# reduktor_ultra_light.net
KiCad netlist of a schematic drawn in EAGLE
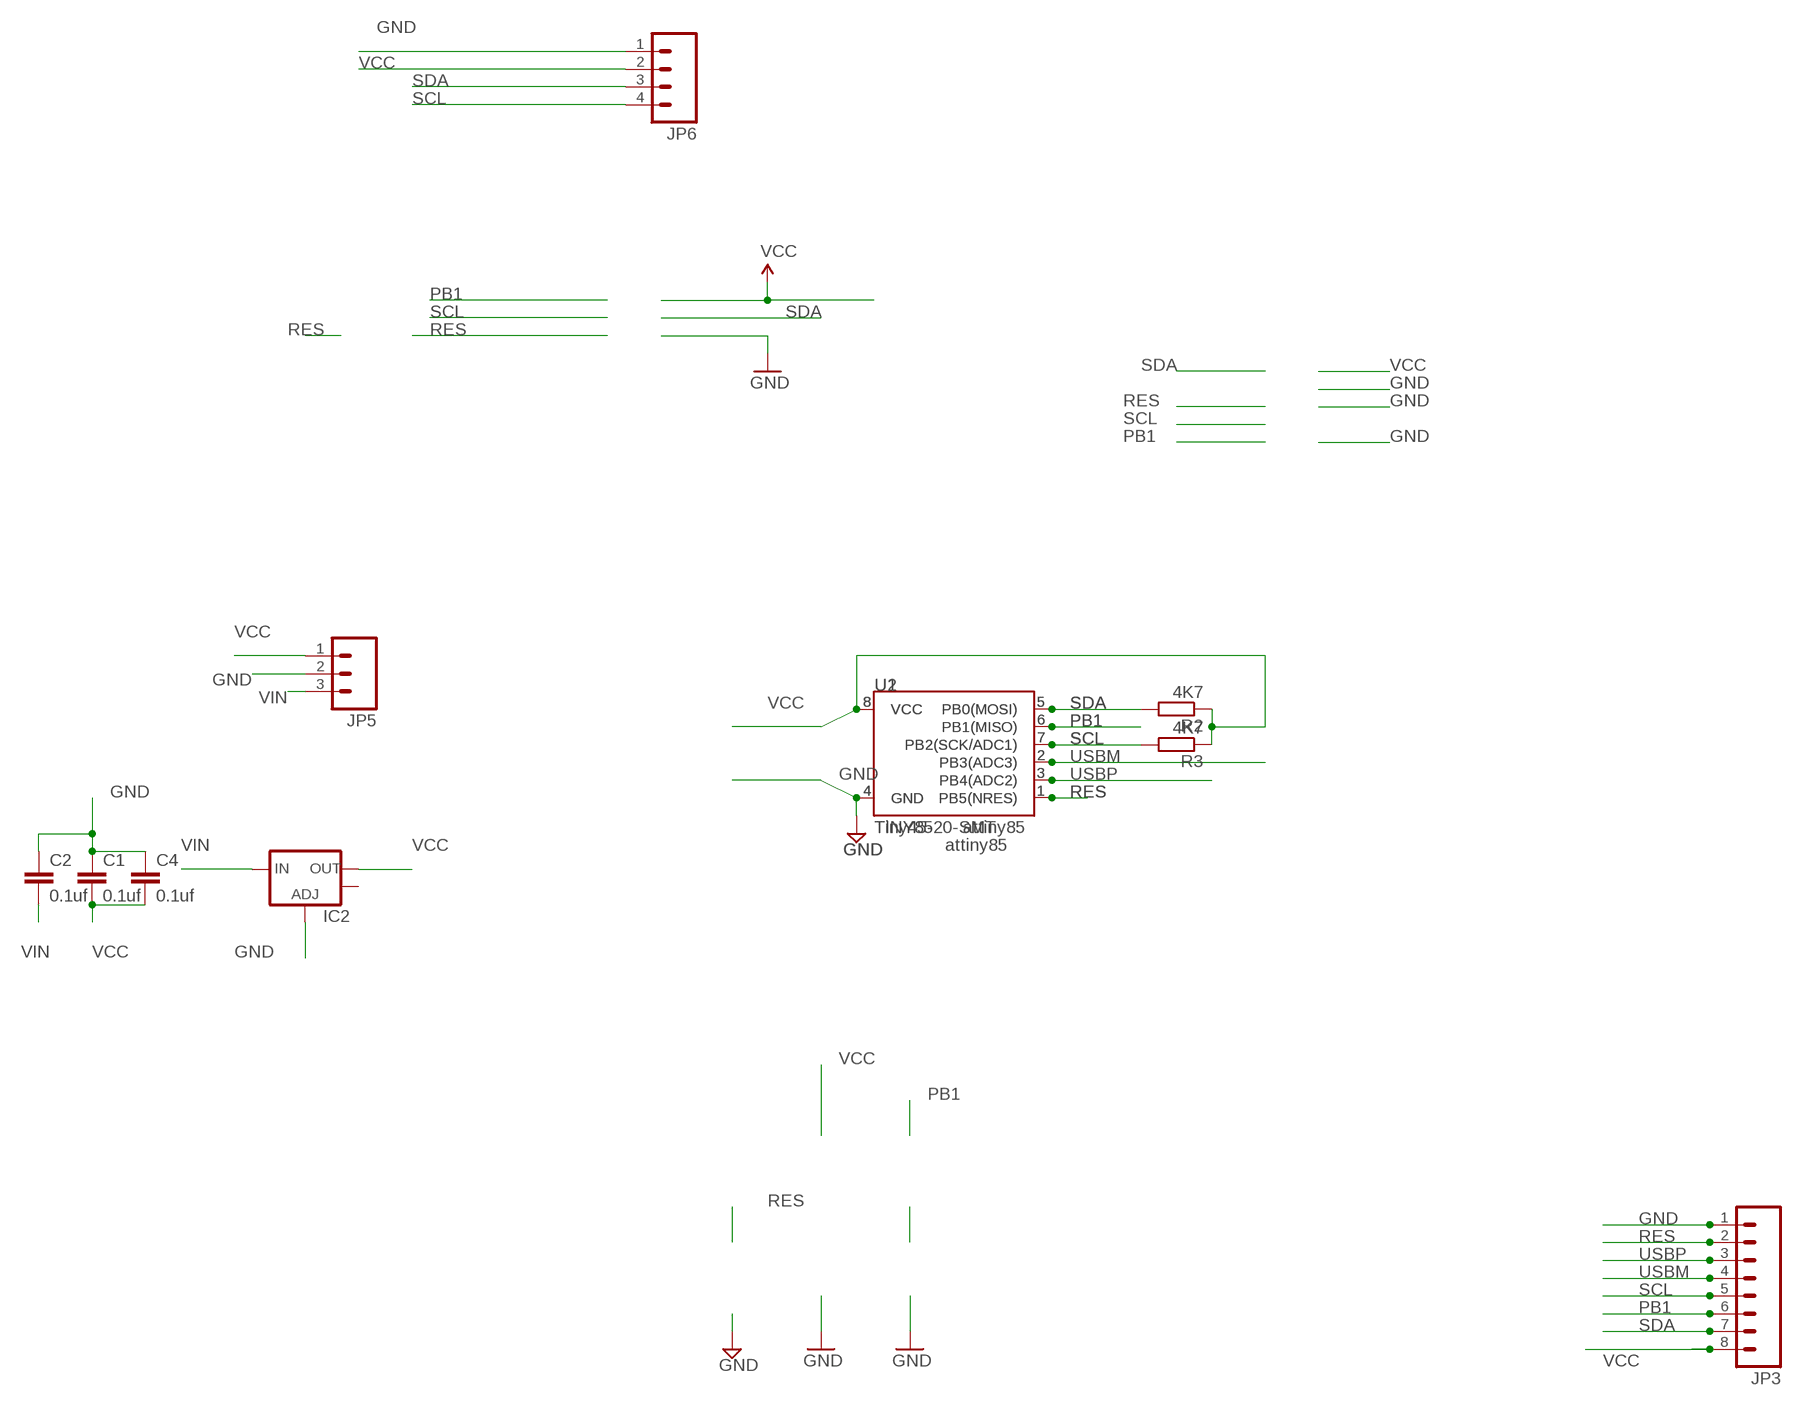
[diagram p0: schematic, sheet 1]

(export (version "E")
  (design (tool "Eeschema 10.0.6"))
  (components
    (comp (ref "C1")
      (value "0.1uf")
      (footprint "eagle-import:0603-CAP")
      (libsource (lib "eagle-import") (part "CAP0603-CAP"))
    )
    (comp (ref "C2")
      (value "0.1uf")
      (footprint "eagle-import:0603-CAP")
      (libsource (lib "eagle-import") (part "CAP0603-CAP"))
    )
    (comp (ref "C4")
      (value "0.1uf")
      (footprint "eagle-import:0603-CAP")
      (libsource (lib "eagle-import") (part "CAP0603-CAP"))
    )
    (comp (ref "IC2")
      (value "V_REG_LM1117SOT223")
      (footprint "eagle-import:SOT223")
      (libsource (lib "eagle-import") (part "V_REG_LM1117SOT223"))
    )
    (comp (ref "JP3")
      (value "M08LOCK")
      (footprint "eagle-import:1X08_LOCK")
      (libsource (lib "eagle-import") (part "M08LOCK"))
    )
    (comp (ref "JP5")
      (value "M03LOCK")
      (footprint "eagle-import:1X03_LOCK")
      (libsource (lib "eagle-import") (part "M03LOCK"))
    )
    (comp (ref "JP6")
      (value "M04PTH")
      (footprint "eagle-import:1X04")
      (libsource (lib "eagle-import") (part "M04PTH"))
    )
    (comp (ref "R2")
      (value "4K7")
      (footprint "eagle-import:R0603")
      (libsource (lib "eagle-import") (part "R-EU_R0603"))
    )
    (comp (ref "R3")
      (value "4K7")
      (footprint "eagle-import:R0603")
      (libsource (lib "eagle-import") (part "R-EU_R0603"))
    )
    (comp (ref "U1")
      (value "TINY85")
      (footprint "eagle-import:DIP08")
      (libsource (lib "eagle-import") (part "ATTINY45TINY45-20-DIP"))
    )
    (comp (ref "U2")
      (value "Tiny45-20-SMT")
      (footprint "eagle-import:SO08-EIAJ")
      (libsource (lib "eagle-import") (part "ATTINY45TINY45-20-SMT"))
    )
  )
  (nets
    (net (code "1") (name "/PB1") (class "Default")
      (node (ref "JP3") (pin "6") (pinfunction "6_6") (pintype "passive"))
      (node (ref "U1") (pin "6") (pinfunction "PB1(MISO)_6") (pintype "bidirectional"))
      (node (ref "U2") (pin "6") (pinfunction "PB1(MISO)_6") (pintype "bidirectional"))
    )
    (net (code "2") (name "/RES") (class "Default")
      (node (ref "JP3") (pin "2") (pinfunction "2_2") (pintype "passive"))
      (node (ref "U1") (pin "1") (pinfunction "PB5(NRES)_1") (pintype "bidirectional"))
      (node (ref "U2") (pin "1") (pinfunction "PB5(NRES)_1") (pintype "bidirectional"))
    )
    (net (code "3") (name "/SCL") (class "Default")
      (node (ref "JP3") (pin "5") (pinfunction "5_5") (pintype "passive"))
      (node (ref "JP6") (pin "4") (pinfunction "4_4") (pintype "passive"))
      (node (ref "R3") (pin "2") (pinfunction "2_2") (pintype "passive"))
      (node (ref "U1") (pin "7") (pinfunction "PB2(SCK/ADC1)_7") (pintype "bidirectional"))
      (node (ref "U2") (pin "7") (pinfunction "PB2(SCK/ADC1)_7") (pintype "bidirectional"))
    )
    (net (code "4") (name "/SDA") (class "Default")
      (node (ref "JP3") (pin "7") (pinfunction "7_7") (pintype "passive"))
      (node (ref "JP6") (pin "3") (pinfunction "3_3") (pintype "passive"))
      (node (ref "R2") (pin "2") (pinfunction "2_2") (pintype "passive"))
      (node (ref "U1") (pin "5") (pinfunction "PB0(MOSI)_5") (pintype "bidirectional"))
      (node (ref "U2") (pin "5") (pinfunction "PB0(MOSI)_5") (pintype "bidirectional"))
    )
    (net (code "5") (name "/USBM") (class "Default")
      (node (ref "JP3") (pin "4") (pinfunction "4_4") (pintype "passive"))
      (node (ref "U1") (pin "2") (pinfunction "PB3(ADC3)_2") (pintype "bidirectional"))
      (node (ref "U2") (pin "2") (pinfunction "PB3(ADC3)_2") (pintype "bidirectional"))
    )
    (net (code "6") (name "/USBP") (class "Default")
      (node (ref "JP3") (pin "3") (pinfunction "3_3") (pintype "passive"))
      (node (ref "U1") (pin "3") (pinfunction "PB4(ADC2)_3") (pintype "bidirectional"))
      (node (ref "U2") (pin "3") (pinfunction "PB4(ADC2)_3") (pintype "bidirectional"))
    )
    (net (code "7") (name "/VIN") (class "Default")
      (node (ref "C2") (pin "2") (pinfunction "2_2") (pintype "passive"))
      (node (ref "IC2") (pin "3") (pinfunction "IN_3") (pintype "input"))
      (node (ref "JP5") (pin "3") (pinfunction "3_3") (pintype "passive"))
    )
    (net (code "8") (name "GND") (class "Default")
      (node (ref "C1") (pin "1") (pinfunction "1_1") (pintype "passive"))
      (node (ref "C2") (pin "1") (pinfunction "1_1") (pintype "passive"))
      (node (ref "C4") (pin "1") (pinfunction "1_1") (pintype "passive"))
      (node (ref "IC2") (pin "1") (pinfunction "ADJ_1") (pintype "input"))
      (node (ref "JP3") (pin "1") (pinfunction "1_1") (pintype "passive"))
      (node (ref "JP5") (pin "2") (pinfunction "2_2") (pintype "passive"))
      (node (ref "JP6") (pin "1") (pinfunction "1_1") (pintype "passive"))
      (node (ref "U1") (pin "4") (pinfunction "GND_4") (pintype "bidirectional"))
      (node (ref "U2") (pin "4") (pinfunction "GND_4") (pintype "bidirectional"))
    )
    (net (code "9") (name "VCC") (class "Default")
      (node (ref "C1") (pin "2") (pinfunction "2_2") (pintype "passive"))
      (node (ref "C4") (pin "2") (pinfunction "2_2") (pintype "passive"))
      (node (ref "IC2") (pin "2") (pinfunction "OUT_2") (pintype "output"))
      (node (ref "JP3") (pin "8") (pinfunction "8_8") (pintype "passive"))
      (node (ref "JP5") (pin "1") (pinfunction "1_1") (pintype "passive"))
      (node (ref "JP6") (pin "2") (pinfunction "2_2") (pintype "passive"))
      (node (ref "R2") (pin "1") (pinfunction "1_1") (pintype "passive"))
      (node (ref "R3") (pin "1") (pinfunction "1_1") (pintype "passive"))
      (node (ref "U1") (pin "8") (pinfunction "VCC_8") (pintype "bidirectional"))
      (node (ref "U2") (pin "8") (pinfunction "VCC_8") (pintype "bidirectional"))
    )
    (net (code "10") (name "unconnected-(IC2-OUT-Pad4)") (class "Default")
      (node (ref "IC2") (pin "4") (pinfunction "OUT_4") (pintype "output"))
    )
  )
)
